# Peripherals.net
KiCad netlist of a schematic drawn in Altium Designer
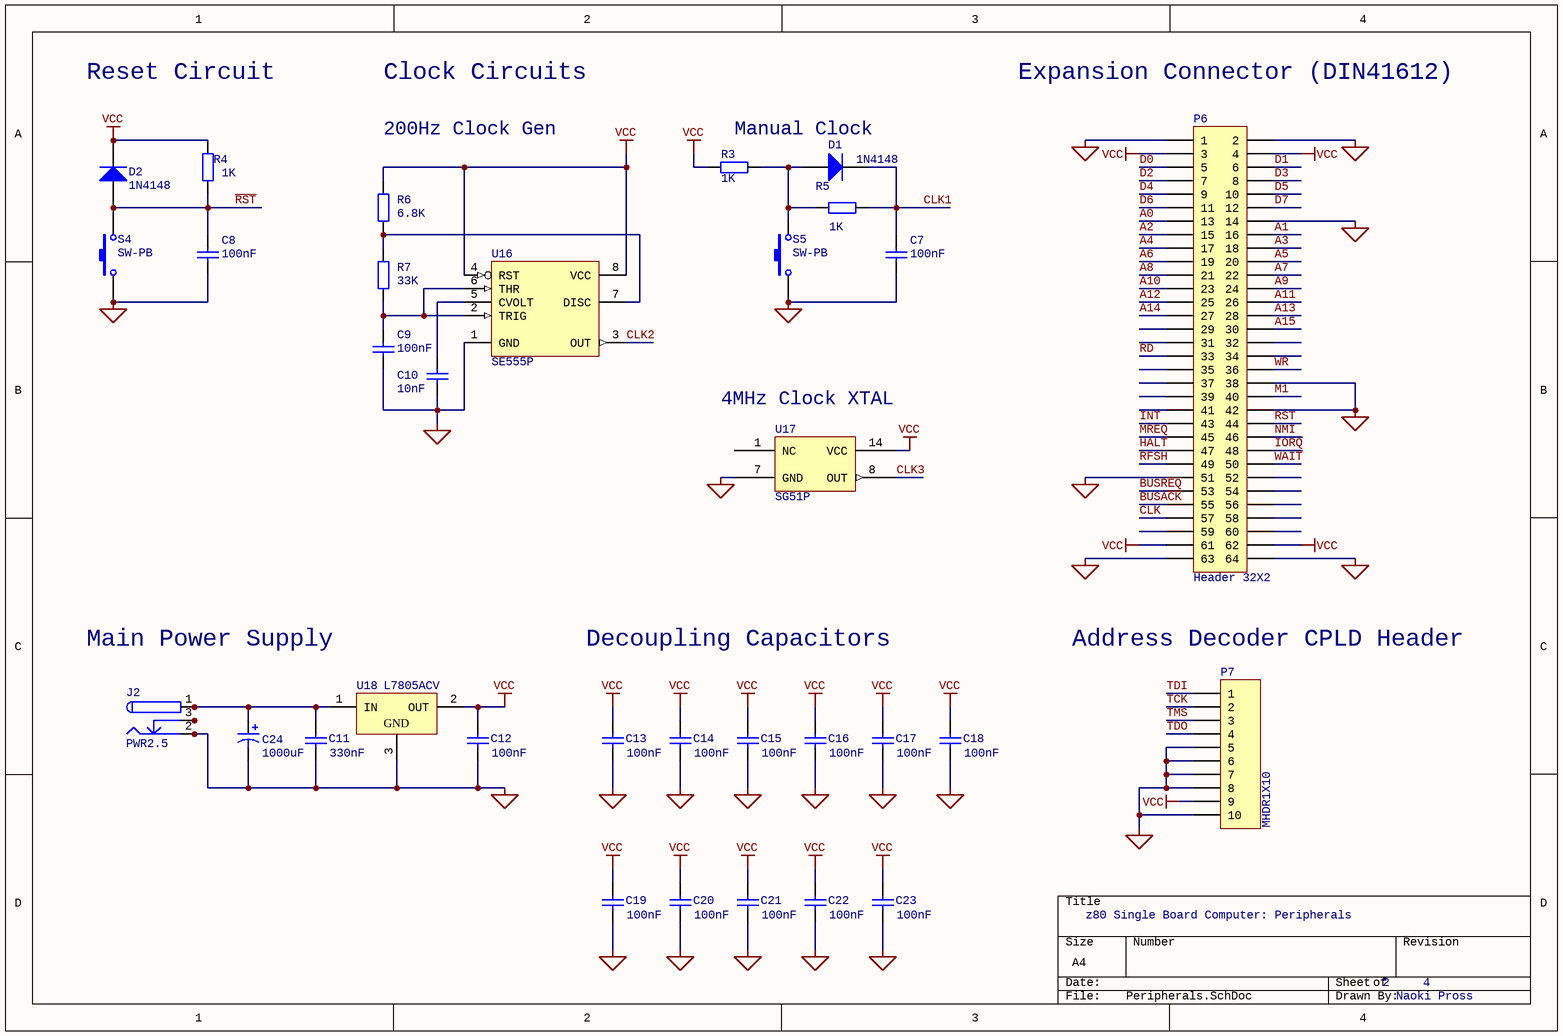
[diagram p0: Peripherals.SchDoc]

(export (version "E")
  (design (tool "Eeschema 10.0.6"))
  (components
    (comp (ref "C7")
      (value "100nF")
      (footprint "RAD-0.1")
      (description "Capacitor")
      (fields (field (name "Comment") "Cap") (field (name "PUBLISHER") "Altium Limited"))
      (libsource (lib "Miscellaneous Devices") (part "Cap"))
    )
    (comp (ref "C8")
      (value "100nF")
      (footprint "RAD-0.1")
      (description "Capacitor")
      (fields (field (name "Comment") "Cap") (field (name "PUBLISHER") "Altium Limited"))
      (libsource (lib "Miscellaneous Devices") (part "Cap"))
    )
    (comp (ref "C9")
      (value "100nF")
      (footprint "RAD-0.1")
      (description "Capacitor")
      (fields (field (name "Comment") "Cap") (field (name "PUBLISHER") "Altium Limited"))
      (libsource (lib "Miscellaneous Devices") (part "Cap"))
    )
    (comp (ref "C10")
      (value "10nF")
      (footprint "RAD-0.4")
      (description "Capacitor")
      (fields (field (name "Comment") "Cap") (field (name "PUBLISHER") "Altium Limited"))
      (libsource (lib "Miscellaneous Devices") (part "Cap"))
    )
    (comp (ref "C11")
      (value "330nF")
      (footprint "RAD-0.3")
      (description "Capacitor")
      (fields (field (name "Comment") "Cap") (field (name "PUBLISHER") "Altium Limited"))
      (libsource (lib "Miscellaneous Devices") (part "Cap"))
    )
    (comp (ref "C12")
      (value "100nF")
      (footprint "RAD-0.1")
      (description "Capacitor")
      (fields (field (name "Comment") "Cap") (field (name "PUBLISHER") "Altium Limited"))
      (libsource (lib "Miscellaneous Devices") (part "Cap"))
    )
    (comp (ref "C13")
      (value "100nF")
      (footprint "RAD-0.1")
      (description "Capacitor")
      (fields (field (name "Comment") "Cap") (field (name "PUBLISHER") "Altium Limited"))
      (libsource (lib "Miscellaneous Devices") (part "Cap"))
    )
    (comp (ref "C14")
      (value "100nF")
      (footprint "RAD-0.1")
      (description "Capacitor")
      (fields (field (name "Comment") "Cap") (field (name "PUBLISHER") "Altium Limited"))
      (libsource (lib "Miscellaneous Devices") (part "Cap"))
    )
    (comp (ref "C15")
      (value "100nF")
      (footprint "RAD-0.1")
      (description "Capacitor")
      (fields (field (name "Comment") "Cap") (field (name "PUBLISHER") "Altium Limited"))
      (libsource (lib "Miscellaneous Devices") (part "Cap"))
    )
    (comp (ref "C16")
      (value "100nF")
      (footprint "RAD-0.1")
      (description "Capacitor")
      (fields (field (name "Comment") "Cap") (field (name "PUBLISHER") "Altium Limited"))
      (libsource (lib "Miscellaneous Devices") (part "Cap"))
    )
    (comp (ref "C17")
      (value "100nF")
      (footprint "RAD-0.1")
      (description "Capacitor")
      (fields (field (name "Comment") "Cap") (field (name "PUBLISHER") "Altium Limited"))
      (libsource (lib "Miscellaneous Devices") (part "Cap"))
    )
    (comp (ref "C18")
      (value "100nF")
      (footprint "RAD-0.1")
      (description "Capacitor")
      (fields (field (name "Comment") "Cap") (field (name "PUBLISHER") "Altium Limited"))
      (libsource (lib "Miscellaneous Devices") (part "Cap"))
    )
    (comp (ref "C19")
      (value "100nF")
      (footprint "RAD-0.1")
      (description "Capacitor")
      (fields (field (name "Comment") "Cap") (field (name "PUBLISHER") "Altium Limited"))
      (libsource (lib "Miscellaneous Devices") (part "Cap"))
    )
    (comp (ref "C20")
      (value "100nF")
      (footprint "RAD-0.1")
      (description "Capacitor")
      (fields (field (name "Comment") "Cap") (field (name "PUBLISHER") "Altium Limited"))
      (libsource (lib "Miscellaneous Devices") (part "Cap"))
    )
    (comp (ref "C21")
      (value "100nF")
      (footprint "RAD-0.1")
      (description "Capacitor")
      (fields (field (name "Comment") "Cap") (field (name "PUBLISHER") "Altium Limited"))
      (libsource (lib "Miscellaneous Devices") (part "Cap"))
    )
    (comp (ref "C22")
      (value "100nF")
      (footprint "RAD-0.1")
      (description "Capacitor")
      (fields (field (name "Comment") "Cap") (field (name "PUBLISHER") "Altium Limited"))
      (libsource (lib "Miscellaneous Devices") (part "Cap"))
    )
    (comp (ref "C23")
      (value "100nF")
      (footprint "RAD-0.1")
      (description "Capacitor")
      (fields (field (name "Comment") "Cap") (field (name "PUBLISHER") "Altium Limited"))
      (libsource (lib "Miscellaneous Devices") (part "Cap"))
    )
    (comp (ref "C24")
      (value "1000uF")
      (footprint "RB5-10.5")
      (description "Polarized Capacitor (Radial)")
      (fields (field (name "Comment") "Cap Pol1") (field (name "PUBLISHER") "Altium Limited"))
      (libsource (lib "Miscellaneous Devices") (part "Cap Pol1"))
    )
    (comp (ref "D1")
      (value "1N4148")
      (footprint "DO-35")
      (description "High Conductance Fast Diode")
      (fields (field (name "PUBLISHER") "Altium Limited"))
      (libsource (lib "Miscellaneous Devices") (part "Diode 1N4148"))
    )
    (comp (ref "D2")
      (value "1N4148")
      (footprint "DO-35")
      (description "High Conductance Fast Diode")
      (fields (field (name "PUBLISHER") "Altium Limited"))
      (libsource (lib "Miscellaneous Devices") (part "Diode 1N4148"))
    )
    (comp (ref "J2")
      (value "PWR2.5")
      (footprint "MainBoard:KLD-0202")
      (description "Low Voltage Power Supply Connector")
      (fields (field (name "PUBLISHER") "Altium Limited"))
      (libsource (lib "Miscellaneous Connectors") (part "PWR2.5"))
    )
    (comp (ref "P6")
      (value "Header 32X2")
      (footprint "0973264X804")
      (description "Header, 32-Pin, Dual row")
      (fields (field (name "PUBLISHER") "Altium Limited"))
      (libsource (lib "z80uPC") (part "Header 32X2"))
    )
    (comp (ref "P7")
      (value "MHDR1X10")
      (footprint "HDR5x2_SOCK")
      (description "Header, 10-Pin")
      (fields (field (name "PUBLISHER") "Altium Limited"))
      (libsource (lib "Miscellaneous Connectors") (part "MHDR1X10"))
    )
    (comp (ref "R3")
      (value "1K")
      (footprint "AXIAL-0.4")
      (description "Resistor")
      (fields (field (name "Comment") "Res2") (field (name "PUBLISHER") "Altium Limited"))
      (libsource (lib "") (part "Res2_1"))
    )
    (comp (ref "R4")
      (value "1K")
      (footprint "AXIAL-0.4")
      (description "Resistor")
      (fields (field (name "Comment") "Res2") (field (name "PUBLISHER") "Altium Limited"))
      (libsource (lib "Miscellaneous Devices") (part "Res2"))
    )
    (comp (ref "R5")
      (value "1K")
      (footprint "AXIAL-0.4")
      (description "Resistor")
      (fields (field (name "Comment") "Res2") (field (name "PUBLISHER") "Altium Limited"))
      (libsource (lib "") (part "Res2_2"))
    )
    (comp (ref "R6")
      (value "6.8K")
      (footprint "AXIAL-0.4")
      (description "Resistor")
      (fields (field (name "Comment") "Res2") (field (name "PUBLISHER") "Altium Limited"))
      (libsource (lib "Miscellaneous Devices") (part "Res2"))
    )
    (comp (ref "R7")
      (value "33K")
      (footprint "AXIAL-0.4")
      (description "Resistor")
      (fields (field (name "Comment") "Res2") (field (name "PUBLISHER") "Altium Limited"))
      (libsource (lib "Miscellaneous Devices") (part "Res2"))
    )
    (comp (ref "S4")
      (value "SW-PB")
      (footprint "DPST-4")
      (description "Switch")
      (fields (field (name "PUBLISHER") "Altium Limited"))
      (libsource (lib "Miscellaneous Devices") (part "SW-PB"))
    )
    (comp (ref "S5")
      (value "SW-PB")
      (footprint "DPST-4")
      (description "Switch")
      (fields (field (name "PUBLISHER") "Altium Limited"))
      (libsource (lib "Miscellaneous Devices") (part "SW-PB"))
    )
    (comp (ref "U16")
      (value "SE555P")
      (footprint "P008")
      (description "Precision Timer")
      (fields (field (name "PUBLISHER") "Altium Limited"))
      (libsource (lib "TI Analog Timer Circuit") (part "SE555P"))
    )
    (comp (ref "U17")
      (value "SG51P")
      (footprint "DIP14")
      (description "4.000000  MHz High Frequency Oscillator")
      (libsource (lib "Seiko Epson Oscillator") (part "SG51P"))
    )
    (comp (ref "U18")
      (value "L7805ACV")
      (footprint "TO220ABN")
      (description "Precision 1A Regulator")
      (fields (field (name "PUBLISHER") "Altium Limited"))
      (libsource (lib "ST Power Mgt Voltage Regulator") (part "L7805ACV"))
    )
  )
  (nets
    (net (code "1") (name "/A0") (class "Default")
      (node (ref "P6") (pin "13") (pinfunction "13_13") (pintype "passive"))
    )
    (net (code "2") (name "/A1") (class "Default")
      (node (ref "P6") (pin "16") (pinfunction "16_16") (pintype "passive"))
    )
    (net (code "3") (name "/A2") (class "Default")
      (node (ref "P6") (pin "15") (pinfunction "15_15") (pintype "passive"))
    )
    (net (code "4") (name "/A3") (class "Default")
      (node (ref "P6") (pin "18") (pinfunction "18_18") (pintype "passive"))
    )
    (net (code "5") (name "/A4") (class "Default")
      (node (ref "P6") (pin "17") (pinfunction "17_17") (pintype "passive"))
    )
    (net (code "6") (name "/A5") (class "Default")
      (node (ref "P6") (pin "20") (pinfunction "20_20") (pintype "passive"))
    )
    (net (code "7") (name "/A6") (class "Default")
      (node (ref "P6") (pin "19") (pinfunction "19_19") (pintype "passive"))
    )
    (net (code "8") (name "/A7") (class "Default")
      (node (ref "P6") (pin "22") (pinfunction "22_22") (pintype "passive"))
    )
    (net (code "9") (name "/A8") (class "Default")
      (node (ref "P6") (pin "21") (pinfunction "21_21") (pintype "passive"))
    )
    (net (code "10") (name "/A9") (class "Default")
      (node (ref "P6") (pin "24") (pinfunction "24_24") (pintype "passive"))
    )
    (net (code "11") (name "/A10") (class "Default")
      (node (ref "P6") (pin "23") (pinfunction "23_23") (pintype "passive"))
    )
    (net (code "12") (name "/A11") (class "Default")
      (node (ref "P6") (pin "26") (pinfunction "26_26") (pintype "passive"))
    )
    (net (code "13") (name "/A12") (class "Default")
      (node (ref "P6") (pin "25") (pinfunction "25_25") (pintype "passive"))
    )
    (net (code "14") (name "/A13") (class "Default")
      (node (ref "P6") (pin "28") (pinfunction "28_28") (pintype "passive"))
    )
    (net (code "15") (name "/A14") (class "Default")
      (node (ref "P6") (pin "27") (pinfunction "27_27") (pintype "passive"))
    )
    (net (code "16") (name "/A15") (class "Default")
      (node (ref "P6") (pin "30") (pinfunction "30_30") (pintype "passive"))
    )
    (net (code "17") (name "/CLK") (class "Default")
      (node (ref "P6") (pin "57") (pinfunction "57_57") (pintype "passive"))
    )
    (net (code "18") (name "/CLK1") (class "Default")
      (node (ref "C7") (pin "2") (pinfunction "2_2") (pintype "passive"))
      (node (ref "D1") (pin "2") (pinfunction "K_2") (pintype "passive"))
      (node (ref "R5") (pin "2") (pinfunction "2_2") (pintype "passive"))
    )
    (net (code "19") (name "/CLK2") (class "Default")
      (node (ref "U16") (pin "3") (pinfunction "OUT_3") (pintype "output"))
    )
    (net (code "20") (name "/CLK3") (class "Default")
      (node (ref "U17") (pin "8") (pinfunction "OUT_8") (pintype "output"))
    )
    (net (code "21") (name "/D0") (class "Default")
      (node (ref "P6") (pin "5") (pinfunction "5_5") (pintype "passive"))
    )
    (net (code "22") (name "/D1") (class "Default")
      (node (ref "P6") (pin "6") (pinfunction "6_6") (pintype "passive"))
    )
    (net (code "23") (name "/D2") (class "Default")
      (node (ref "P6") (pin "7") (pinfunction "7_7") (pintype "passive"))
    )
    (net (code "24") (name "/D3") (class "Default")
      (node (ref "P6") (pin "8") (pinfunction "8_8") (pintype "passive"))
    )
    (net (code "25") (name "/D4") (class "Default")
      (node (ref "P6") (pin "9") (pinfunction "9_9") (pintype "passive"))
    )
    (net (code "26") (name "/D5") (class "Default")
      (node (ref "P6") (pin "10") (pinfunction "10_10") (pintype "passive"))
    )
    (net (code "27") (name "/D6") (class "Default")
      (node (ref "P6") (pin "11") (pinfunction "11_11") (pintype "passive"))
    )
    (net (code "28") (name "/D7") (class "Default")
      (node (ref "P6") (pin "12") (pinfunction "12_12") (pintype "passive"))
    )
    (net (code "29") (name "/NMI") (class "Default")
      (node (ref "P6") (pin "46") (pinfunction "46_46") (pintype "passive"))
    )
    (net (code "30") (name "/TCK") (class "Default")
      (node (ref "P7") (pin "2") (pinfunction "2_2") (pintype "passive"))
    )
    (net (code "31") (name "/TDI") (class "Default")
      (node (ref "P7") (pin "1") (pinfunction "1_1") (pintype "passive"))
    )
    (net (code "32") (name "/TDO") (class "Default")
      (node (ref "P7") (pin "4") (pinfunction "4_4") (pintype "passive"))
    )
    (net (code "33") (name "/TMS") (class "Default")
      (node (ref "P7") (pin "3") (pinfunction "3_3") (pintype "passive"))
    )
    (net (code "34") (name "/~{BUSACK}") (class "Default")
      (node (ref "P6") (pin "55") (pinfunction "55_55") (pintype "passive"))
    )
    (net (code "35") (name "/~{BUSREQ}") (class "Default")
      (node (ref "P6") (pin "53") (pinfunction "53_53") (pintype "passive"))
    )
    (net (code "36") (name "/~{HALT}") (class "Default")
      (node (ref "P6") (pin "47") (pinfunction "47_47") (pintype "passive"))
    )
    (net (code "37") (name "/~{INT}") (class "Default")
      (node (ref "P6") (pin "43") (pinfunction "43_43") (pintype "passive"))
    )
    (net (code "38") (name "/~{IORQ}") (class "Default")
      (node (ref "P6") (pin "48") (pinfunction "48_48") (pintype "passive"))
    )
    (net (code "39") (name "/~{M1}") (class "Default")
      (node (ref "P6") (pin "40") (pinfunction "40_40") (pintype "passive"))
    )
    (net (code "40") (name "/~{MREQ}") (class "Default")
      (node (ref "P6") (pin "45") (pinfunction "45_45") (pintype "passive"))
    )
    (net (code "41") (name "/~{RD}") (class "Default")
      (node (ref "P6") (pin "33") (pinfunction "33_33") (pintype "passive"))
    )
    (net (code "42") (name "/~{RFSH}") (class "Default")
      (node (ref "P6") (pin "49") (pinfunction "49_49") (pintype "passive"))
    )
    (net (code "43") (name "/~{RST}") (class "Default")
      (node (ref "C8") (pin "2") (pinfunction "2_2") (pintype "passive"))
      (node (ref "D2") (pin "1") (pinfunction "A_1") (pintype "passive"))
      (node (ref "P6") (pin "44") (pinfunction "44_44") (pintype "passive"))
      (node (ref "R4") (pin "1") (pinfunction "1_1") (pintype "passive"))
      (node (ref "S4") (pin "2") (pinfunction "2_2") (pintype "passive"))
    )
    (net (code "44") (name "/~{WAIT}") (class "Default")
      (node (ref "P6") (pin "50") (pinfunction "50_50") (pintype "passive"))
    )
    (net (code "45") (name "/~{WR}") (class "Default")
      (node (ref "P6") (pin "36") (pinfunction "36_36") (pintype "passive"))
    )
    (net (code "46") (name "GND") (class "Default")
      (node (ref "C10") (pin "1") (pinfunction "1_1") (pintype "passive"))
      (node (ref "C11") (pin "1") (pinfunction "1_1") (pintype "passive"))
      (node (ref "C12") (pin "1") (pinfunction "1_1") (pintype "passive"))
      (node (ref "C13") (pin "1") (pinfunction "1_1") (pintype "passive"))
      (node (ref "C14") (pin "1") (pinfunction "1_1") (pintype "passive"))
      (node (ref "C15") (pin "1") (pinfunction "1_1") (pintype "passive"))
      (node (ref "C16") (pin "1") (pinfunction "1_1") (pintype "passive"))
      (node (ref "C17") (pin "1") (pinfunction "1_1") (pintype "passive"))
      (node (ref "C18") (pin "1") (pinfunction "1_1") (pintype "passive"))
      (node (ref "C19") (pin "1") (pinfunction "1_1") (pintype "passive"))
      (node (ref "C20") (pin "1") (pinfunction "1_1") (pintype "passive"))
      (node (ref "C21") (pin "1") (pinfunction "1_1") (pintype "passive"))
      (node (ref "C22") (pin "1") (pinfunction "1_1") (pintype "passive"))
      (node (ref "C23") (pin "1") (pinfunction "1_1") (pintype "passive"))
      (node (ref "C24") (pin "2") (pinfunction "2_2") (pintype "passive"))
      (node (ref "C7") (pin "1") (pinfunction "1_1") (pintype "passive"))
      (node (ref "C8") (pin "1") (pinfunction "1_1") (pintype "passive"))
      (node (ref "C9") (pin "1") (pinfunction "1_1") (pintype "passive"))
      (node (ref "J2") (pin "2") (pinfunction "2_2") (pintype "power_in"))
      (node (ref "J2") (pin "2A") (pinfunction "2A_2A") (pintype "power_in"))
      (node (ref "J2") (pin "2B") (pinfunction "2B_2B") (pintype "power_in"))
      (node (ref "P6") (pin "1") (pinfunction "1_1") (pintype "passive"))
      (node (ref "P6") (pin "14") (pinfunction "14_14") (pintype "passive"))
      (node (ref "P6") (pin "2") (pinfunction "2_2") (pintype "passive"))
      (node (ref "P6") (pin "38") (pinfunction "38_38") (pintype "passive"))
      (node (ref "P6") (pin "42") (pinfunction "42_42") (pintype "passive"))
      (node (ref "P6") (pin "51") (pinfunction "51_51") (pintype "passive"))
      (node (ref "P6") (pin "63") (pinfunction "63_63") (pintype "passive"))
      (node (ref "P6") (pin "64") (pinfunction "64_64") (pintype "passive"))
      (node (ref "P7") (pin "10") (pinfunction "10_10") (pintype "passive"))
      (node (ref "P7") (pin "5") (pinfunction "5_5") (pintype "passive"))
      (node (ref "P7") (pin "6") (pinfunction "6_6") (pintype "passive"))
      (node (ref "P7") (pin "7") (pinfunction "7_7") (pintype "passive"))
      (node (ref "P7") (pin "8") (pinfunction "8_8") (pintype "passive"))
      (node (ref "S4") (pin "1") (pinfunction "1_1") (pintype "passive"))
      (node (ref "S5") (pin "1") (pinfunction "1_1") (pintype "passive"))
      (node (ref "U16") (pin "1") (pinfunction "GND_1") (pintype "power_in"))
      (node (ref "U17") (pin "7") (pinfunction "GND_7") (pintype "power_in"))
      (node (ref "U18") (pin "3") (pinfunction "GND_3") (pintype "power_in"))
    )
    (net (code "47") (name "Net-(D1-A)") (class "Default")
      (node (ref "D1") (pin "1") (pinfunction "A_1") (pintype "passive"))
      (node (ref "R3") (pin "1") (pinfunction "1_1") (pintype "passive"))
      (node (ref "R5") (pin "1") (pinfunction "1_1") (pintype "passive"))
      (node (ref "S5") (pin "2") (pinfunction "2_2") (pintype "passive"))
    )
    (net (code "48") (name "Net-(J2-Pad3)") (class "Default")
      (node (ref "J2") (pin "3") (pinfunction "3_3") (pintype "power_in"))
      (node (ref "J2") (pin "3A") (pinfunction "3A_3A") (pintype "power_in"))
      (node (ref "J2") (pin "3B") (pinfunction "3B_3B") (pintype "power_in"))
    )
    (net (code "49") (name "Net-(U16-CVOLT)") (class "Default")
      (node (ref "C10") (pin "2") (pinfunction "2_2") (pintype "passive"))
      (node (ref "U16") (pin "5") (pinfunction "CVOLT_5") (pintype "passive"))
    )
    (net (code "50") (name "Net-(U16-DISC)") (class "Default")
      (node (ref "R6") (pin "1") (pinfunction "1_1") (pintype "passive"))
      (node (ref "R7") (pin "2") (pinfunction "2_2") (pintype "passive"))
      (node (ref "U16") (pin "7") (pinfunction "DISC_7") (pintype "open_collector"))
    )
    (net (code "51") (name "Net-(U16-THR)") (class "Default")
      (node (ref "C9") (pin "2") (pinfunction "2_2") (pintype "passive"))
      (node (ref "R7") (pin "1") (pinfunction "1_1") (pintype "passive"))
      (node (ref "U16") (pin "2") (pinfunction "TRIG_2") (pintype "input"))
      (node (ref "U16") (pin "6") (pinfunction "THR_6") (pintype "input"))
    )
    (net (code "52") (name "Net-(U18-IN)") (class "Default")
      (node (ref "C11") (pin "2") (pinfunction "2_2") (pintype "passive"))
      (node (ref "C24") (pin "1") (pinfunction "1_1") (pintype "passive"))
      (node (ref "J2") (pin "1") (pinfunction "1_1") (pintype "power_in"))
      (node (ref "J2") (pin "1A") (pinfunction "1A_1A") (pintype "power_in"))
      (node (ref "J2") (pin "1B") (pinfunction "1B_1B") (pintype "power_in"))
      (node (ref "U18") (pin "1") (pinfunction "IN_1") (pintype "power_in"))
    )
    (net (code "53") (name "VCC") (class "Default")
      (node (ref "C12") (pin "2") (pinfunction "2_2") (pintype "passive"))
      (node (ref "C13") (pin "2") (pinfunction "2_2") (pintype "passive"))
      (node (ref "C14") (pin "2") (pinfunction "2_2") (pintype "passive"))
      (node (ref "C15") (pin "2") (pinfunction "2_2") (pintype "passive"))
      (node (ref "C16") (pin "2") (pinfunction "2_2") (pintype "passive"))
      (node (ref "C17") (pin "2") (pinfunction "2_2") (pintype "passive"))
      (node (ref "C18") (pin "2") (pinfunction "2_2") (pintype "passive"))
      (node (ref "C19") (pin "2") (pinfunction "2_2") (pintype "passive"))
      (node (ref "C20") (pin "2") (pinfunction "2_2") (pintype "passive"))
      (node (ref "C21") (pin "2") (pinfunction "2_2") (pintype "passive"))
      (node (ref "C22") (pin "2") (pinfunction "2_2") (pintype "passive"))
      (node (ref "C23") (pin "2") (pinfunction "2_2") (pintype "passive"))
      (node (ref "D2") (pin "2") (pinfunction "K_2") (pintype "passive"))
      (node (ref "P6") (pin "3") (pinfunction "3_3") (pintype "passive"))
      (node (ref "P6") (pin "4") (pinfunction "4_4") (pintype "passive"))
      (node (ref "P6") (pin "61") (pinfunction "61_61") (pintype "passive"))
      (node (ref "P6") (pin "62") (pinfunction "62_62") (pintype "passive"))
      (node (ref "P7") (pin "9") (pinfunction "9_9") (pintype "passive"))
      (node (ref "R3") (pin "2") (pinfunction "2_2") (pintype "passive"))
      (node (ref "R4") (pin "2") (pinfunction "2_2") (pintype "passive"))
      (node (ref "R6") (pin "2") (pinfunction "2_2") (pintype "passive"))
      (node (ref "U16") (pin "4") (pinfunction "RST_4") (pintype "input"))
      (node (ref "U16") (pin "8") (pinfunction "VCC_8") (pintype "power_in"))
      (node (ref "U17") (pin "14") (pinfunction "VCC_14") (pintype "power_in"))
      (node (ref "U18") (pin "2") (pinfunction "OUT_2") (pintype "power_in"))
    )
    (net (code "54") (name "unconnected-(P6-Pad29)") (class "Default")
      (node (ref "P6") (pin "29") (pinfunction "29_29") (pintype "passive"))
    )
    (net (code "55") (name "unconnected-(P6-Pad31)") (class "Default")
      (node (ref "P6") (pin "31") (pinfunction "31_31") (pintype "passive"))
    )
    (net (code "56") (name "unconnected-(P6-Pad32)") (class "Default")
      (node (ref "P6") (pin "32") (pinfunction "32_32") (pintype "passive"))
    )
    (net (code "57") (name "unconnected-(P6-Pad34)") (class "Default")
      (node (ref "P6") (pin "34") (pinfunction "34_34") (pintype "passive"))
    )
    (net (code "58") (name "unconnected-(P6-Pad35)") (class "Default")
      (node (ref "P6") (pin "35") (pinfunction "35_35") (pintype "passive"))
    )
    (net (code "59") (name "unconnected-(P6-Pad37)") (class "Default")
      (node (ref "P6") (pin "37") (pinfunction "37_37") (pintype "passive"))
    )
    (net (code "60") (name "unconnected-(P6-Pad39)") (class "Default")
      (node (ref "P6") (pin "39") (pinfunction "39_39") (pintype "passive"))
    )
    (net (code "61") (name "unconnected-(P6-Pad41)") (class "Default")
      (node (ref "P6") (pin "41") (pinfunction "41_41") (pintype "passive"))
    )
    (net (code "62") (name "unconnected-(P6-Pad52)") (class "Default")
      (node (ref "P6") (pin "52") (pinfunction "52_52") (pintype "passive"))
    )
    (net (code "63") (name "unconnected-(P6-Pad54)") (class "Default")
      (node (ref "P6") (pin "54") (pinfunction "54_54") (pintype "passive"))
    )
    (net (code "64") (name "unconnected-(P6-Pad56)") (class "Default")
      (node (ref "P6") (pin "56") (pinfunction "56_56") (pintype "passive"))
    )
    (net (code "65") (name "unconnected-(P6-Pad58)") (class "Default")
      (node (ref "P6") (pin "58") (pinfunction "58_58") (pintype "passive"))
    )
    (net (code "66") (name "unconnected-(P6-Pad59)") (class "Default")
      (node (ref "P6") (pin "59") (pinfunction "59_59") (pintype "passive"))
    )
    (net (code "67") (name "unconnected-(P6-Pad60)") (class "Default")
      (node (ref "P6") (pin "60") (pinfunction "60_60") (pintype "passive"))
    )
    (net (code "68") (name "unconnected-(U17-NC-Pad1)") (class "Default")
      (node (ref "U17") (pin "1") (pinfunction "NC_1") (pintype "passive"))
    )
  )
)
